# M-BOX.net
KiCad netlist of a schematic drawn in Altium Designer
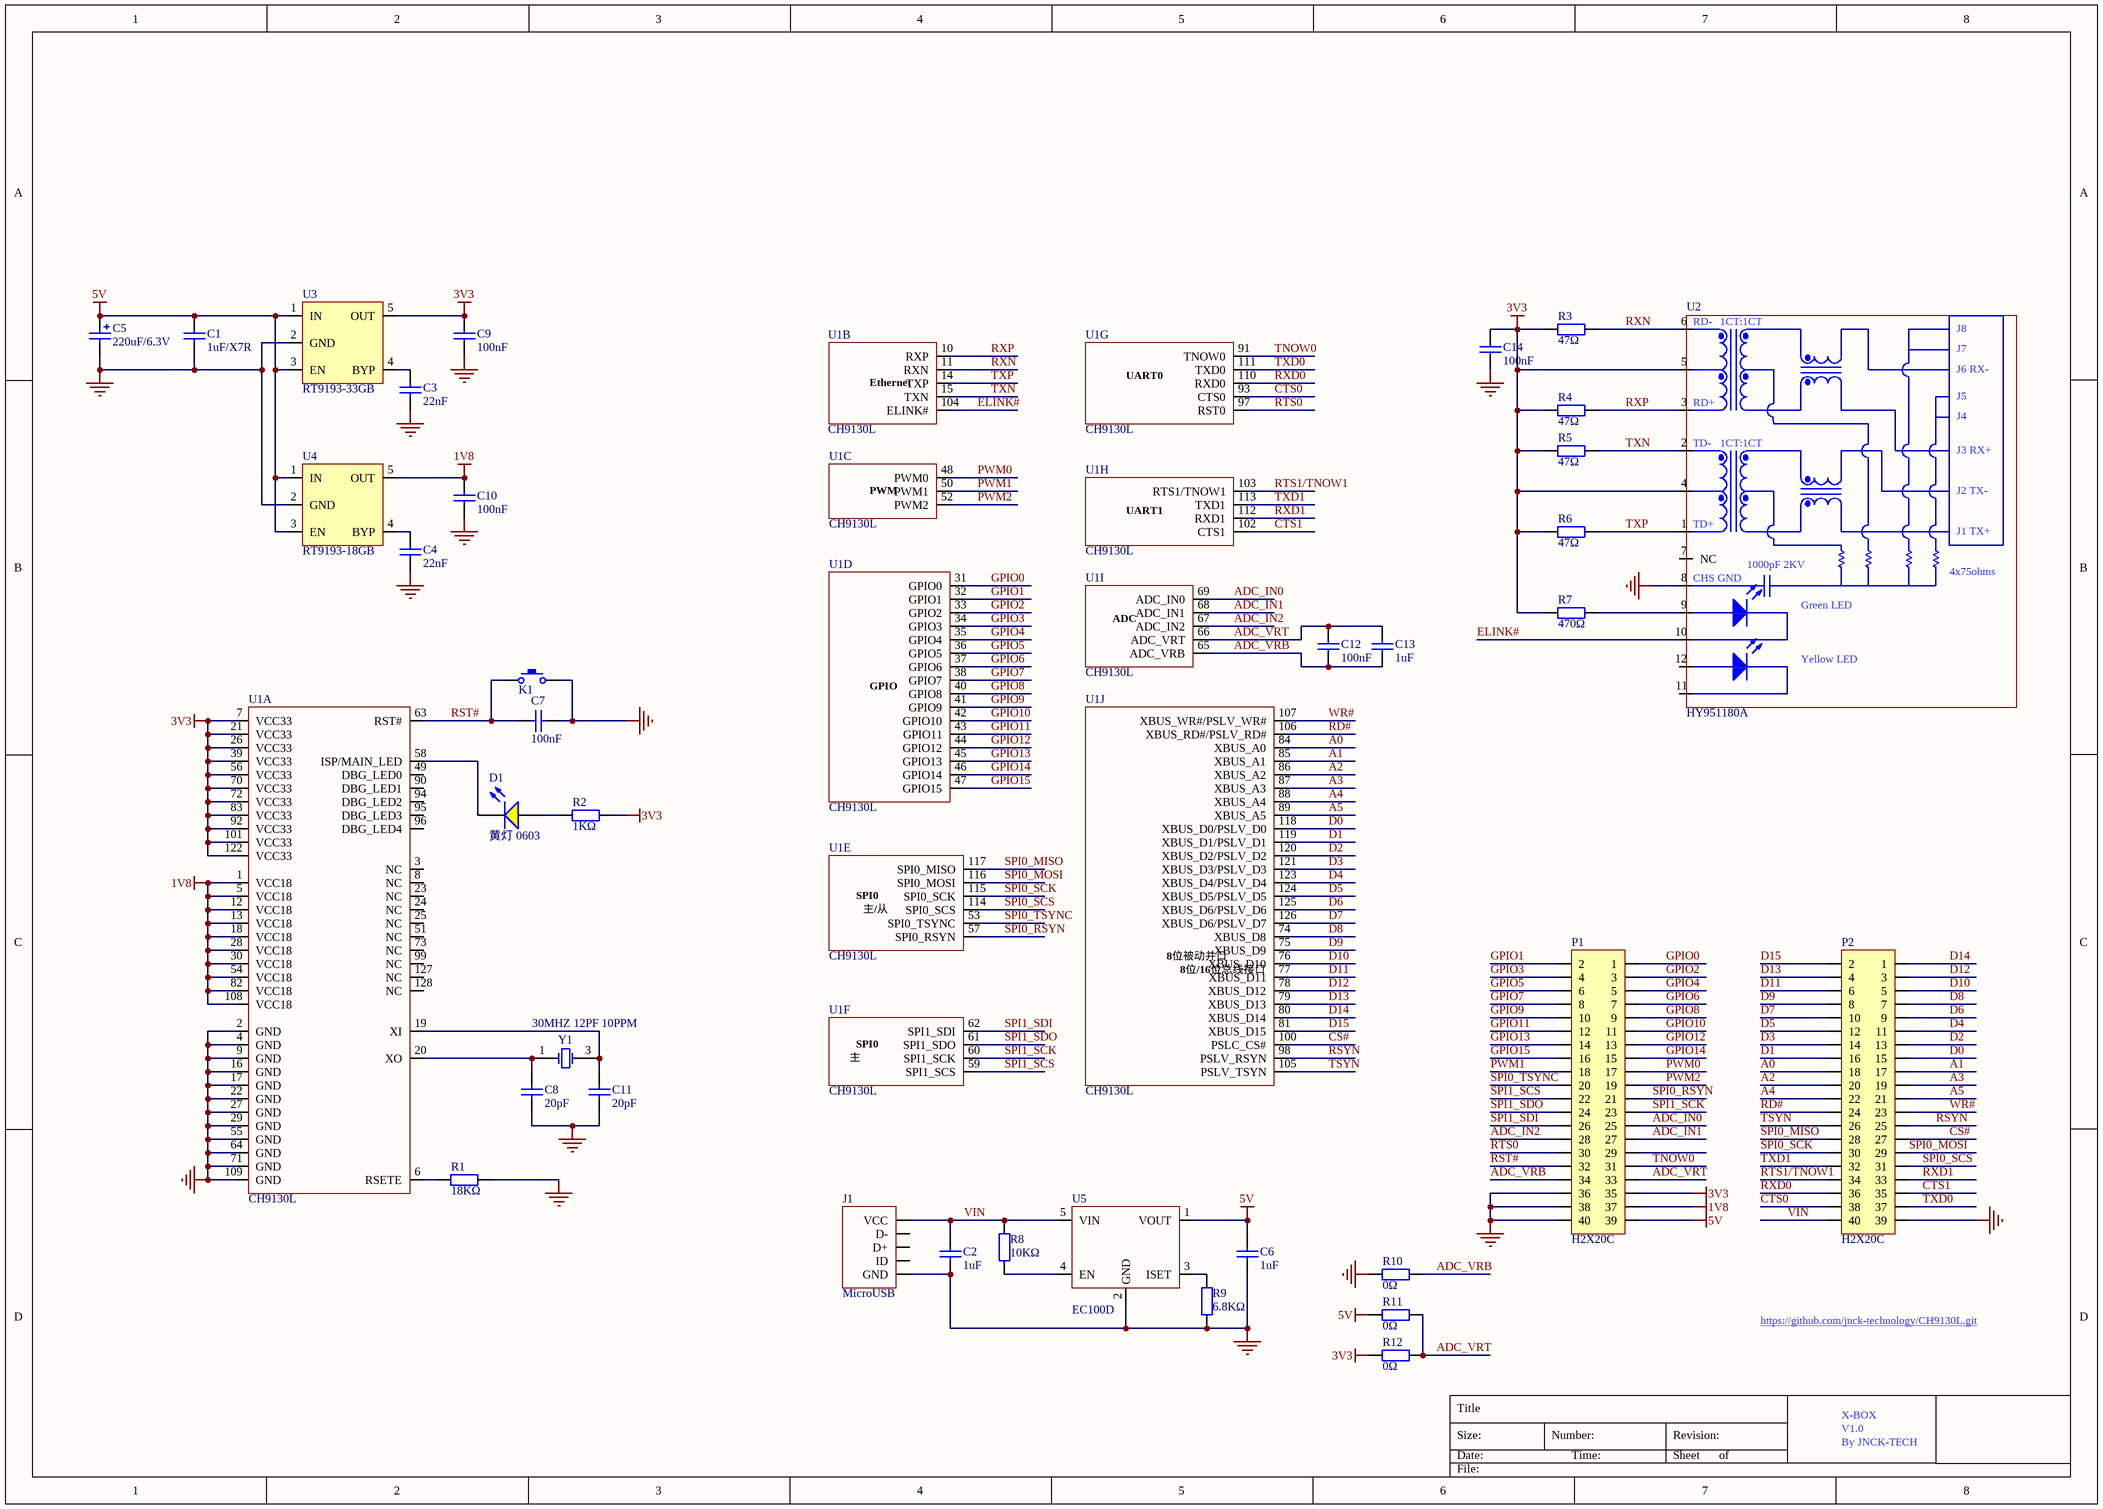
[diagram p0: M-BOX.SchDoc]

(export (version "E")
  (design (tool "Eeschema 10.0.6"))
  (components
    (comp (ref "C1")
      (value "1uF/X7R")
      (footprint "LC-0603_C")
      (description "贴片电容")
      (libsource (lib "Miscellaneous Devices LC") (part "0603 1uF (105) 10% 50V"))
    )
    (comp (ref "C2")
      (value "1uF")
      (footprint "LC-0603_C")
      (description "贴片电容")
      (libsource (lib "Miscellaneous Devices LC") (part "0603 1uF (105) 10% 50V"))
    )
    (comp (ref "C3")
      (value "22nF")
      (footprint "LC-0603_C")
      (description "贴片电容")
      (libsource (lib "Miscellaneous Devices LC") (part "0603 22nF (223) 10% 50V"))
    )
    (comp (ref "C4")
      (value "22nF")
      (footprint "LC-0603_C")
      (description "贴片电容")
      (libsource (lib "Miscellaneous Devices LC") (part "0603 22nF (223) 10% 50V"))
    )
    (comp (ref "C5")
      (value "220uF/6.3V")
      (footprint "LC-CASE-A_3216")
      (description "钽电容")
      (libsource (lib "Miscellaneous Devices LC") (part "3216 10uF (106) 10% 16V"))
    )
    (comp (ref "C6")
      (value "1uF")
      (footprint "LC-0603_C")
      (description "贴片电容")
      (libsource (lib "Miscellaneous Devices LC") (part "0603 1uF (105) 10% 50V"))
    )
    (comp (ref "C7")
      (value "100nF")
      (footprint "LC-0603_C")
      (description "贴片电容")
      (libsource (lib "Miscellaneous Devices LC") (part "0603 100nF (104) 10% 50V"))
    )
    (comp (ref "C8")
      (value "20pF")
      (footprint "LC-0603_C")
      (description "贴片电容")
      (libsource (lib "Miscellaneous Devices LC") (part "0603 20pF (200) 5% 50V"))
    )
    (comp (ref "C9")
      (value "100nF")
      (footprint "LC-0603_C")
      (description "贴片电容")
      (libsource (lib "Miscellaneous Devices LC") (part "0603 100nF (104) 10% 50V"))
    )
    (comp (ref "C10")
      (value "100nF")
      (footprint "LC-0603_C")
      (description "贴片电容")
      (libsource (lib "Miscellaneous Devices LC") (part "0603 100nF (104) 10% 50V"))
    )
    (comp (ref "C11")
      (value "20pF")
      (footprint "LC-0603_C")
      (description "贴片电容")
      (libsource (lib "Miscellaneous Devices LC") (part "0603 20pF (200) 5% 50V"))
    )
    (comp (ref "C12")
      (value "100nF")
      (footprint "LC-0603_C")
      (description "贴片电容")
      (libsource (lib "Miscellaneous Devices LC") (part "0603 100nF (104) 10% 50V"))
    )
    (comp (ref "C13")
      (value "1uF")
      (footprint "LC-0603_C")
      (description "贴片电容")
      (libsource (lib "Miscellaneous Devices LC") (part "0603 1uF (105) 10% 50V"))
    )
    (comp (ref "C14")
      (value "100nF")
      (footprint "LC-0603_C")
      (description "贴片电容")
      (libsource (lib "Miscellaneous Devices LC") (part "0603 100nF (104) 10% 50V"))
    )
    (comp (ref "D1")
      (value "黄灯 0603")
      (footprint "LC-0603_LED_S1")
      (description "发光二极管")
      (libsource (lib "Miscellaneous Devices LC") (part "0603 黄灯"))
    )
    (comp (ref "J1")
      (value "MicroUSB")
      (footprint "MicroUSB")
      (libsource (lib "MY-Standard-Library-AD") (part "MicroUSB"))
    )
    (comp (ref "K1")
      (value "TS-1107U")
      (footprint "TS-1107U")
      (description "轻触按钮")
      (fields (field (name "MANUFACTURER") "皓宇電子"))
      (libsource (lib "MY-Standard-Library-AD") (part "SW_TS-1107U"))
    )
    (comp (ref "P1")
      (value "H2X20C")
      (footprint "H2X20C")
      (description "排母/2.54mm 2*20P 长脚排座")
      (libsource (lib "MY-Standard-Library-AD") (part "H2X20C"))
    )
    (comp (ref "P2")
      (value "H2X20C")
      (footprint "H2X20C")
      (description "排母/2.54mm 2*20P 长脚排座")
      (libsource (lib "MY-Standard-Library-AD") (part "H2X20C"))
    )
    (comp (ref "R1")
      (value "18KΩ")
      (footprint "LC-0603_R")
      (description "贴片电阻")
      (libsource (lib "Miscellaneous Devices LC") (part "0603 18KΩ (1802) 1%"))
    )
    (comp (ref "R2")
      (value "1KΩ")
      (footprint "LC-0603_R")
      (description "贴片电阻")
      (libsource (lib "Miscellaneous Devices LC") (part "0603 1KΩ (1001) 1%"))
    )
    (comp (ref "R3")
      (value "47Ω")
      (footprint "LC-0603_R")
      (description "贴片电阻")
      (libsource (lib "Miscellaneous Devices LC") (part "0603 47Ω (47R0) 1%"))
    )
    (comp (ref "R4")
      (value "47Ω")
      (footprint "LC-0603_R")
      (description "贴片电阻")
      (libsource (lib "Miscellaneous Devices LC") (part "0603 47Ω (47R0) 1%"))
    )
    (comp (ref "R5")
      (value "47Ω")
      (footprint "LC-0603_R")
      (description "贴片电阻")
      (libsource (lib "Miscellaneous Devices LC") (part "0603 47Ω (47R0) 1%"))
    )
    (comp (ref "R6")
      (value "47Ω")
      (footprint "LC-0603_R")
      (description "贴片电阻")
      (libsource (lib "Miscellaneous Devices LC") (part "0603 47Ω (47R0) 1%"))
    )
    (comp (ref "R7")
      (value "470Ω")
      (footprint "LC-0603_R")
      (description "贴片电阻")
      (libsource (lib "Miscellaneous Devices LC") (part "0603 470Ω (4700) 1%"))
    )
    (comp (ref "R8")
      (value "10KΩ")
      (footprint "LC-0603_R")
      (description "贴片电阻")
      (libsource (lib "Miscellaneous Devices LC") (part "0603 10KΩ (1002) 1%"))
    )
    (comp (ref "R9")
      (value "6.8KΩ")
      (footprint "LC-0603_R")
      (description "贴片电阻")
      (libsource (lib "Miscellaneous Devices LC") (part "0603 6.8KΩ (6801) 1%"))
    )
    (comp (ref "R10")
      (value "0Ω")
      (footprint "LC-0603_R")
      (description "贴片电阻")
      (libsource (lib "Miscellaneous Devices LC") (part "0603 0Ω (0R0) 1%"))
    )
    (comp (ref "R11")
      (value "0Ω")
      (footprint "LC-0603_R")
      (description "贴片电阻")
      (libsource (lib "Miscellaneous Devices LC") (part "0603 0Ω (0R0) 1%"))
    )
    (comp (ref "R12")
      (value "0Ω")
      (footprint "LC-0603_R")
      (description "贴片电阻")
      (libsource (lib "Miscellaneous Devices LC") (part "0603 0Ω (0R0) 1%"))
    )
    (comp (ref "U1")
      (value "CH9130L")
      (footprint "LC-LQFP-128_14x14x04P")
      (description "以太网扩展多外设接口芯片")
      (fields (field (name "MANUFACTURER") "WCH(南京沁恒)"))
      (libsource (lib "MY-Standard-Library-AD") (part "CH9130L"))
    )
    (comp (ref "U2")
      (value "HY951180A")
      (footprint "HY951180A")
      (description "网口")
      (fields (field (name "MANUFACTURER") "HANRUN(汉仁)"))
      (libsource (lib "MY-Standard-Library-AD") (part "HY951180A"))
    )
    (comp (ref "U3")
      (value "RT9193-33GB")
      (footprint "LC-SOT-23-5")
      (description "RT9193 Series 300 mA 3.3 V")
      (libsource (lib "MY-Standard-Library-AD") (part "RT9193-33GB"))
    )
    (comp (ref "U4")
      (value "RT9193-18GB")
      (footprint "LC-SOT-23-5")
      (description "RT9193 Series 1.8V 300 mA")
      (libsource (lib "MY-Standard-Library-AD") (part "RT9193-18GB"))
    )
    (comp (ref "U5")
      (value "EC100D")
      (footprint "LC-SOT-23-5")
      (description "短路、过流保护芯片")
      (fields (field (name "MANUFACTURER") "FM富满"))
      (libsource (lib "MY-Standard-Library-AD") (part "EC100D"))
    )
    (comp (ref "Y1")
      (value "30MHZ 12PF 10PPM")
      (footprint "LC-SMD-3225_4P")
      (description "贴片晶振")
      (libsource (lib "Miscellaneous Devices LC") (part "SMD-3225_4P  16MHZ 9PF 10PPM"))
    )
  )
  (nets
    (net (code "1") (name "/A0") (class "Default")
      (node (ref "P2") (pin "18") (pinfunction "18_18") (pintype "passive"))
      (node (ref "U1") (pin "84") (pinfunction "XBUS_A0_84") (pintype "passive"))
    )
    (net (code "2") (name "/A1") (class "Default")
      (node (ref "P2") (pin "17") (pinfunction "17_17") (pintype "passive"))
      (node (ref "U1") (pin "85") (pinfunction "XBUS_A1_85") (pintype "passive"))
    )
    (net (code "3") (name "/A2") (class "Default")
      (node (ref "P2") (pin "20") (pinfunction "20_20") (pintype "passive"))
      (node (ref "U1") (pin "86") (pinfunction "XBUS_A2_86") (pintype "passive"))
    )
    (net (code "4") (name "/A3") (class "Default")
      (node (ref "P2") (pin "19") (pinfunction "19_19") (pintype "passive"))
      (node (ref "U1") (pin "87") (pinfunction "XBUS_A3_87") (pintype "passive"))
    )
    (net (code "5") (name "/A4") (class "Default")
      (node (ref "P2") (pin "22") (pinfunction "22_22") (pintype "passive"))
      (node (ref "U1") (pin "88") (pinfunction "XBUS_A4_88") (pintype "passive"))
    )
    (net (code "6") (name "/A5") (class "Default")
      (node (ref "P2") (pin "21") (pinfunction "21_21") (pintype "passive"))
      (node (ref "U1") (pin "89") (pinfunction "XBUS_A5_89") (pintype "passive"))
    )
    (net (code "7") (name "/ADC_IN0") (class "Default")
      (node (ref "P1") (pin "25") (pinfunction "25_25") (pintype "passive"))
      (node (ref "U1") (pin "69") (pinfunction "ADC_IN0_69") (pintype "passive"))
    )
    (net (code "8") (name "/ADC_IN1") (class "Default")
      (node (ref "P1") (pin "27") (pinfunction "27_27") (pintype "passive"))
      (node (ref "U1") (pin "68") (pinfunction "ADC_IN1_68") (pintype "passive"))
    )
    (net (code "9") (name "/ADC_IN2") (class "Default")
      (node (ref "P1") (pin "28") (pinfunction "28_28") (pintype "passive"))
      (node (ref "U1") (pin "67") (pinfunction "ADC_IN2_67") (pintype "passive"))
    )
    (net (code "10") (name "/ADC_VRB") (class "Default")
      (node (ref "C12") (pin "1") (pinfunction "1_1") (pintype "passive"))
      (node (ref "C13") (pin "1") (pinfunction "1_1") (pintype "passive"))
      (node (ref "P1") (pin "34") (pinfunction "34_34") (pintype "passive"))
      (node (ref "R10") (pin "2") (pinfunction "2_2") (pintype "passive"))
      (node (ref "U1") (pin "65") (pinfunction "ADC_VRB_65") (pintype "passive"))
    )
    (net (code "11") (name "/ADC_VRT") (class "Default")
      (node (ref "C12") (pin "2") (pinfunction "2_2") (pintype "passive"))
      (node (ref "C13") (pin "2") (pinfunction "2_2") (pintype "passive"))
      (node (ref "P1") (pin "33") (pinfunction "33_33") (pintype "passive"))
      (node (ref "R11") (pin "2") (pinfunction "2_2") (pintype "passive"))
      (node (ref "R12") (pin "2") (pinfunction "2_2") (pintype "passive"))
      (node (ref "U1") (pin "66") (pinfunction "ADC_VRT_66") (pintype "passive"))
    )
    (net (code "12") (name "/CS#") (class "Default")
      (node (ref "P2") (pin "27") (pinfunction "27_27") (pintype "passive"))
      (node (ref "U1") (pin "100") (pinfunction "PSLC_CS#_100") (pintype "passive"))
    )
    (net (code "13") (name "/CTS0") (class "Default")
      (node (ref "P2") (pin "38") (pinfunction "38_38") (pintype "passive"))
      (node (ref "U1") (pin "93") (pinfunction "CTS0_93") (pintype "passive"))
    )
    (net (code "14") (name "/CTS1") (class "Default")
      (node (ref "P2") (pin "35") (pinfunction "35_35") (pintype "passive"))
      (node (ref "U1") (pin "102") (pinfunction "CTS1_102") (pintype "passive"))
    )
    (net (code "15") (name "/D0") (class "Default")
      (node (ref "P2") (pin "15") (pinfunction "15_15") (pintype "passive"))
      (node (ref "U1") (pin "118") (pinfunction "XBUS_D0/PSLV_D0_118") (pintype "passive"))
    )
    (net (code "16") (name "/D1") (class "Default")
      (node (ref "P2") (pin "16") (pinfunction "16_16") (pintype "passive"))
      (node (ref "U1") (pin "119") (pinfunction "XBUS_D1/PSLV_D1_119") (pintype "passive"))
    )
    (net (code "17") (name "/D2") (class "Default")
      (node (ref "P2") (pin "13") (pinfunction "13_13") (pintype "passive"))
      (node (ref "U1") (pin "120") (pinfunction "XBUS_D2/PSLV_D2_120") (pintype "passive"))
    )
    (net (code "18") (name "/D3") (class "Default")
      (node (ref "P2") (pin "14") (pinfunction "14_14") (pintype "passive"))
      (node (ref "U1") (pin "121") (pinfunction "XBUS_D3/PSLV_D3_121") (pintype "passive"))
    )
    (net (code "19") (name "/D4") (class "Default")
      (node (ref "P2") (pin "11") (pinfunction "11_11") (pintype "passive"))
      (node (ref "U1") (pin "123") (pinfunction "XBUS_D4/PSLV_D4_123") (pintype "passive"))
    )
    (net (code "20") (name "/D5") (class "Default")
      (node (ref "P2") (pin "12") (pinfunction "12_12") (pintype "passive"))
      (node (ref "U1") (pin "124") (pinfunction "XBUS_D5/PSLV_D5_124") (pintype "passive"))
    )
    (net (code "21") (name "/D6") (class "Default")
      (node (ref "P2") (pin "9") (pinfunction "9_9") (pintype "passive"))
      (node (ref "U1") (pin "125") (pinfunction "XBUS_D6/PSLV_D6_125") (pintype "passive"))
    )
    (net (code "22") (name "/D7") (class "Default")
      (node (ref "P2") (pin "10") (pinfunction "10_10") (pintype "passive"))
      (node (ref "U1") (pin "126") (pinfunction "XBUS_D6/PSLV_D7_126") (pintype "passive"))
    )
    (net (code "23") (name "/D8") (class "Default")
      (node (ref "P2") (pin "7") (pinfunction "7_7") (pintype "passive"))
      (node (ref "U1") (pin "74") (pinfunction "XBUS_D8_74") (pintype "passive"))
    )
    (net (code "24") (name "/D9") (class "Default")
      (node (ref "P2") (pin "8") (pinfunction "8_8") (pintype "passive"))
      (node (ref "U1") (pin "75") (pinfunction "XBUS_D9_75") (pintype "passive"))
    )
    (net (code "25") (name "/D10") (class "Default")
      (node (ref "P2") (pin "5") (pinfunction "5_5") (pintype "passive"))
      (node (ref "U1") (pin "76") (pinfunction "XBUS_D10_76") (pintype "passive"))
    )
    (net (code "26") (name "/D11") (class "Default")
      (node (ref "P2") (pin "6") (pinfunction "6_6") (pintype "passive"))
      (node (ref "U1") (pin "77") (pinfunction "XBUS_D11_77") (pintype "passive"))
    )
    (net (code "27") (name "/D12") (class "Default")
      (node (ref "P2") (pin "3") (pinfunction "3_3") (pintype "passive"))
      (node (ref "U1") (pin "78") (pinfunction "XBUS_D12_78") (pintype "passive"))
    )
    (net (code "28") (name "/D13") (class "Default")
      (node (ref "P2") (pin "4") (pinfunction "4_4") (pintype "passive"))
      (node (ref "U1") (pin "79") (pinfunction "XBUS_D13_79") (pintype "passive"))
    )
    (net (code "29") (name "/D14") (class "Default")
      (node (ref "P2") (pin "1") (pinfunction "1_1") (pintype "passive"))
      (node (ref "U1") (pin "80") (pinfunction "XBUS_D14_80") (pintype "passive"))
    )
    (net (code "30") (name "/D15") (class "Default")
      (node (ref "P2") (pin "2") (pinfunction "2_2") (pintype "passive"))
      (node (ref "U1") (pin "81") (pinfunction "XBUS_D15_81") (pintype "passive"))
    )
    (net (code "31") (name "/ELINK#") (class "Default")
      (node (ref "U1") (pin "104") (pinfunction "ELINK#_104") (pintype "passive"))
      (node (ref "U2") (pin "10") (pinfunction "10_10") (pintype "passive"))
    )
    (net (code "32") (name "/GPIO0") (class "Default")
      (node (ref "P1") (pin "1") (pinfunction "1_1") (pintype "passive"))
      (node (ref "U1") (pin "31") (pinfunction "GPIO0_31") (pintype "passive"))
    )
    (net (code "33") (name "/GPIO1") (class "Default")
      (node (ref "P1") (pin "2") (pinfunction "2_2") (pintype "passive"))
      (node (ref "U1") (pin "32") (pinfunction "GPIO1_32") (pintype "passive"))
    )
    (net (code "34") (name "/GPIO2") (class "Default")
      (node (ref "P1") (pin "3") (pinfunction "3_3") (pintype "passive"))
      (node (ref "U1") (pin "33") (pinfunction "GPIO2_33") (pintype "passive"))
    )
    (net (code "35") (name "/GPIO3") (class "Default")
      (node (ref "P1") (pin "4") (pinfunction "4_4") (pintype "passive"))
      (node (ref "U1") (pin "34") (pinfunction "GPIO3_34") (pintype "passive"))
    )
    (net (code "36") (name "/GPIO4") (class "Default")
      (node (ref "P1") (pin "5") (pinfunction "5_5") (pintype "passive"))
      (node (ref "U1") (pin "35") (pinfunction "GPIO4_35") (pintype "passive"))
    )
    (net (code "37") (name "/GPIO5") (class "Default")
      (node (ref "P1") (pin "6") (pinfunction "6_6") (pintype "passive"))
      (node (ref "U1") (pin "36") (pinfunction "GPIO5_36") (pintype "passive"))
    )
    (net (code "38") (name "/GPIO6") (class "Default")
      (node (ref "P1") (pin "7") (pinfunction "7_7") (pintype "passive"))
      (node (ref "U1") (pin "37") (pinfunction "GPIO6_37") (pintype "passive"))
    )
    (net (code "39") (name "/GPIO7") (class "Default")
      (node (ref "P1") (pin "8") (pinfunction "8_8") (pintype "passive"))
      (node (ref "U1") (pin "38") (pinfunction "GPIO7_38") (pintype "passive"))
    )
    (net (code "40") (name "/GPIO8") (class "Default")
      (node (ref "P1") (pin "9") (pinfunction "9_9") (pintype "passive"))
      (node (ref "U1") (pin "40") (pinfunction "GPIO8_40") (pintype "passive"))
    )
    (net (code "41") (name "/GPIO9") (class "Default")
      (node (ref "P1") (pin "10") (pinfunction "10_10") (pintype "passive"))
      (node (ref "U1") (pin "41") (pinfunction "GPIO9_41") (pintype "passive"))
    )
    (net (code "42") (name "/GPIO10") (class "Default")
      (node (ref "P1") (pin "11") (pinfunction "11_11") (pintype "passive"))
      (node (ref "U1") (pin "42") (pinfunction "GPIO10_42") (pintype "passive"))
    )
    (net (code "43") (name "/GPIO11") (class "Default")
      (node (ref "P1") (pin "12") (pinfunction "12_12") (pintype "passive"))
      (node (ref "U1") (pin "43") (pinfunction "GPIO11_43") (pintype "passive"))
    )
    (net (code "44") (name "/GPIO12") (class "Default")
      (node (ref "P1") (pin "13") (pinfunction "13_13") (pintype "passive"))
      (node (ref "U1") (pin "44") (pinfunction "GPIO12_44") (pintype "passive"))
    )
    (net (code "45") (name "/GPIO13") (class "Default")
      (node (ref "P1") (pin "14") (pinfunction "14_14") (pintype "passive"))
      (node (ref "U1") (pin "45") (pinfunction "GPIO13_45") (pintype "passive"))
    )
    (net (code "46") (name "/GPIO14") (class "Default")
      (node (ref "P1") (pin "15") (pinfunction "15_15") (pintype "passive"))
      (node (ref "U1") (pin "46") (pinfunction "GPIO14_46") (pintype "passive"))
    )
    (net (code "47") (name "/GPIO15") (class "Default")
      (node (ref "P1") (pin "16") (pinfunction "16_16") (pintype "passive"))
      (node (ref "U1") (pin "47") (pinfunction "GPIO15_47") (pintype "passive"))
    )
    (net (code "48") (name "/PWM0") (class "Default")
      (node (ref "P1") (pin "17") (pinfunction "17_17") (pintype "passive"))
      (node (ref "U1") (pin "48") (pinfunction "PWM0_48") (pintype "passive"))
    )
    (net (code "49") (name "/PWM1") (class "Default")
      (node (ref "P1") (pin "18") (pinfunction "18_18") (pintype "passive"))
      (node (ref "U1") (pin "50") (pinfunction "PWM1_50") (pintype "passive"))
    )
    (net (code "50") (name "/PWM2") (class "Default")
      (node (ref "P1") (pin "19") (pinfunction "19_19") (pintype "passive"))
      (node (ref "U1") (pin "52") (pinfunction "PWM2_52") (pintype "passive"))
    )
    (net (code "51") (name "/RD#") (class "Default")
      (node (ref "P2") (pin "24") (pinfunction "24_24") (pintype "passive"))
      (node (ref "U1") (pin "106") (pinfunction "XBUS_RD#/PSLV_RD#_106") (pintype "passive"))
    )
    (net (code "52") (name "/RST#") (class "Default")
      (node (ref "C7") (pin "2") (pinfunction "2_2") (pintype "passive"))
      (node (ref "K1") (pin "1") (pinfunction "1_1") (pintype "passive"))
      (node (ref "P1") (pin "32") (pinfunction "32_32") (pintype "passive"))
      (node (ref "U1") (pin "63") (pinfunction "RST#_63") (pintype "passive"))
    )
    (net (code "53") (name "/RSYN") (class "Default")
      (node (ref "P2") (pin "25") (pinfunction "25_25") (pintype "passive"))
      (node (ref "U1") (pin "98") (pinfunction "PSLV_RSYN_98") (pintype "passive"))
    )
    (net (code "54") (name "/RTS0") (class "Default")
      (node (ref "P1") (pin "30") (pinfunction "30_30") (pintype "passive"))
      (node (ref "U1") (pin "97") (pinfunction "RST0_97") (pintype "passive"))
    )
    (net (code "55") (name "/RTS1{slash}TNOW1") (class "Default")
      (node (ref "P2") (pin "34") (pinfunction "34_34") (pintype "passive"))
      (node (ref "U1") (pin "103") (pinfunction "RTS1/TNOW1_103") (pintype "passive"))
    )
    (net (code "56") (name "/RXD0") (class "Default")
      (node (ref "P2") (pin "36") (pinfunction "36_36") (pintype "passive"))
      (node (ref "U1") (pin "110") (pinfunction "RXD0_110") (pintype "passive"))
    )
    (net (code "57") (name "/RXD1") (class "Default")
      (node (ref "P2") (pin "33") (pinfunction "33_33") (pintype "passive"))
      (node (ref "U1") (pin "112") (pinfunction "RXD1_112") (pintype "passive"))
    )
    (net (code "58") (name "/RXN") (class "Default")
      (node (ref "R3") (pin "2") (pinfunction "2_2") (pintype "passive"))
      (node (ref "U1") (pin "11") (pinfunction "RXN_11") (pintype "passive"))
      (node (ref "U2") (pin "6") (pinfunction "RD-_6") (pintype "passive"))
    )
    (net (code "59") (name "/RXP") (class "Default")
      (node (ref "R4") (pin "2") (pinfunction "2_2") (pintype "passive"))
      (node (ref "U1") (pin "10") (pinfunction "RXP_10") (pintype "passive"))
      (node (ref "U2") (pin "3") (pinfunction "RD+_3") (pintype "passive"))
    )
    (net (code "60") (name "/SPI0_MISO") (class "Default")
      (node (ref "P2") (pin "28") (pinfunction "28_28") (pintype "passive"))
      (node (ref "U1") (pin "117") (pinfunction "SPI0_MISO_117") (pintype "passive"))
    )
    (net (code "61") (name "/SPI0_MOSI") (class "Default")
      (node (ref "P2") (pin "29") (pinfunction "29_29") (pintype "passive"))
      (node (ref "U1") (pin "116") (pinfunction "SPI0_MOSI_116") (pintype "passive"))
    )
    (net (code "62") (name "/SPI0_RSYN") (class "Default")
      (node (ref "P1") (pin "21") (pinfunction "21_21") (pintype "passive"))
      (node (ref "U1") (pin "57") (pinfunction "SPI0_RSYN_57") (pintype "passive"))
    )
    (net (code "63") (name "/SPI0_SCK") (class "Default")
      (node (ref "P2") (pin "30") (pinfunction "30_30") (pintype "passive"))
      (node (ref "U1") (pin "115") (pinfunction "SPI0_SCK_115") (pintype "passive"))
    )
    (net (code "64") (name "/SPI0_SCS") (class "Default")
      (node (ref "P2") (pin "31") (pinfunction "31_31") (pintype "passive"))
      (node (ref "U1") (pin "114") (pinfunction "SPI0_SCS_114") (pintype "passive"))
    )
    (net (code "65") (name "/SPI0_TSYNC") (class "Default")
      (node (ref "P1") (pin "20") (pinfunction "20_20") (pintype "passive"))
      (node (ref "U1") (pin "53") (pinfunction "SPI0_TSYNC_53") (pintype "passive"))
    )
    (net (code "66") (name "/SPI1_SCK") (class "Default")
      (node (ref "P1") (pin "23") (pinfunction "23_23") (pintype "passive"))
      (node (ref "U1") (pin "60") (pinfunction "SPI1_SCK_60") (pintype "passive"))
    )
    (net (code "67") (name "/SPI1_SCS") (class "Default")
      (node (ref "P1") (pin "22") (pinfunction "22_22") (pintype "passive"))
      (node (ref "U1") (pin "59") (pinfunction "SPI1_SCS_59") (pintype "passive"))
    )
    (net (code "68") (name "/SPI1_SDI") (class "Default")
      (node (ref "P1") (pin "26") (pinfunction "26_26") (pintype "passive"))
      (node (ref "U1") (pin "62") (pinfunction "SPI1_SDI_62") (pintype "passive"))
    )
    (net (code "69") (name "/SPI1_SDO") (class "Default")
      (node (ref "P1") (pin "24") (pinfunction "24_24") (pintype "passive"))
      (node (ref "U1") (pin "61") (pinfunction "SPI1_SDO_61") (pintype "passive"))
    )
    (net (code "70") (name "/TNOW0") (class "Default")
      (node (ref "P1") (pin "31") (pinfunction "31_31") (pintype "passive"))
      (node (ref "U1") (pin "91") (pinfunction "TNOW0_91") (pintype "passive"))
    )
    (net (code "71") (name "/TSYN") (class "Default")
      (node (ref "P2") (pin "26") (pinfunction "26_26") (pintype "passive"))
      (node (ref "U1") (pin "105") (pinfunction "PSLV_TSYN_105") (pintype "passive"))
    )
    (net (code "72") (name "/TXD0") (class "Default")
      (node (ref "P2") (pin "37") (pinfunction "37_37") (pintype "passive"))
      (node (ref "U1") (pin "111") (pinfunction "TXD0_111") (pintype "passive"))
    )
    (net (code "73") (name "/TXD1") (class "Default")
      (node (ref "P2") (pin "32") (pinfunction "32_32") (pintype "passive"))
      (node (ref "U1") (pin "113") (pinfunction "TXD1_113") (pintype "passive"))
    )
    (net (code "74") (name "/TXN") (class "Default")
      (node (ref "R5") (pin "2") (pinfunction "2_2") (pintype "passive"))
      (node (ref "U1") (pin "15") (pinfunction "TXN_15") (pintype "passive"))
      (node (ref "U2") (pin "2") (pinfunction "TD-_2") (pintype "passive"))
    )
    (net (code "75") (name "/TXP") (class "Default")
      (node (ref "R6") (pin "2") (pinfunction "2_2") (pintype "passive"))
      (node (ref "U1") (pin "14") (pinfunction "TXP_14") (pintype "passive"))
      (node (ref "U2") (pin "1") (pinfunction "TD+_1") (pintype "passive"))
    )
    (net (code "76") (name "/VIN") (class "Default")
      (node (ref "C2") (pin "2") (pinfunction "2_2") (pintype "passive"))
      (node (ref "J1") (pin "1") (pinfunction "VCC_1") (pintype "passive"))
      (node (ref "P2") (pin "40") (pinfunction "40_40") (pintype "passive"))
      (node (ref "R8") (pin "2") (pinfunction "2_2") (pintype "passive"))
      (node (ref "U5") (pin "5") (pinfunction "VIN_5") (pintype "passive"))
    )
    (net (code "77") (name "/WR#") (class "Default")
      (node (ref "P2") (pin "23") (pinfunction "23_23") (pintype "passive"))
      (node (ref "U1") (pin "107") (pinfunction "XBUS_WR#/PSLV_WR#_107") (pintype "passive"))
    )
    (net (code "78") (name "1V8") (class "Default")
      (node (ref "C10") (pin "2") (pinfunction "2_2") (pintype "passive"))
      (node (ref "P1") (pin "37") (pinfunction "37_37") (pintype "passive"))
      (node (ref "U1") (pin "1") (pinfunction "VCC18_1") (pintype "passive"))
      (node (ref "U1") (pin "108") (pinfunction "VCC18_108") (pintype "passive"))
      (node (ref "U1") (pin "12") (pinfunction "VCC18_12") (pintype "passive"))
      (node (ref "U1") (pin "13") (pinfunction "VCC18_13") (pintype "passive"))
      (node (ref "U1") (pin "18") (pinfunction "VCC18_18") (pintype "passive"))
      (node (ref "U1") (pin "28") (pinfunction "VCC18_28") (pintype "passive"))
      (node (ref "U1") (pin "30") (pinfunction "VCC18_30") (pintype "passive"))
      (node (ref "U1") (pin "5") (pinfunction "VCC18_5") (pintype "passive"))
      (node (ref "U1") (pin "54") (pinfunction "VCC18_54") (pintype "passive"))
      (node (ref "U1") (pin "82") (pinfunction "VCC18_82") (pintype "passive"))
      (node (ref "U4") (pin "5") (pinfunction "OUT_5") (pintype "passive"))
    )
    (net (code "79") (name "3V3") (class "Default")
      (node (ref "C14") (pin "2") (pinfunction "2_2") (pintype "passive"))
      (node (ref "C9") (pin "2") (pinfunction "2_2") (pintype "passive"))
      (node (ref "P1") (pin "35") (pinfunction "35_35") (pintype "passive"))
      (node (ref "R12") (pin "1") (pinfunction "1_1") (pintype "passive"))
      (node (ref "R2") (pin "2") (pinfunction "2_2") (pintype "passive"))
      (node (ref "R3") (pin "1") (pinfunction "1_1") (pintype "passive"))
      (node (ref "R4") (pin "1") (pinfunction "1_1") (pintype "passive"))
      (node (ref "R5") (pin "1") (pinfunction "1_1") (pintype "passive"))
      (node (ref "R6") (pin "1") (pinfunction "1_1") (pintype "passive"))
      (node (ref "R7") (pin "1") (pinfunction "1_1") (pintype "passive"))
      (node (ref "U1") (pin "101") (pinfunction "VCC33_101") (pintype "passive"))
      (node (ref "U1") (pin "122") (pinfunction "VCC33_122") (pintype "passive"))
      (node (ref "U1") (pin "21") (pinfunction "VCC33_21") (pintype "passive"))
      (node (ref "U1") (pin "26") (pinfunction "VCC33_26") (pintype "passive"))
      (node (ref "U1") (pin "39") (pinfunction "VCC33_39") (pintype "passive"))
      (node (ref "U1") (pin "56") (pinfunction "VCC33_56") (pintype "passive"))
      (node (ref "U1") (pin "7") (pinfunction "VCC33_7") (pintype "passive"))
      (node (ref "U1") (pin "70") (pinfunction "VCC33_70") (pintype "passive"))
      (node (ref "U1") (pin "72") (pinfunction "VCC33_72") (pintype "passive"))
      (node (ref "U1") (pin "83") (pinfunction "VCC33_83") (pintype "passive"))
      (node (ref "U1") (pin "92") (pinfunction "VCC33_92") (pintype "passive"))
      (node (ref "U2") (pin "4") (pinfunction "4_4") (pintype "passive"))
      (node (ref "U2") (pin "5") (pinfunction "5_5") (pintype "passive"))
      (node (ref "U3") (pin "5") (pinfunction "OUT_5") (pintype "passive"))
    )
    (net (code "80") (name "5V") (class "Default")
      (node (ref "C1") (pin "2") (pinfunction "2_2") (pintype "passive"))
      (node (ref "C5") (pin "1") (pinfunction "1_1") (pintype "passive"))
      (node (ref "C6") (pin "2") (pinfunction "2_2") (pintype "passive"))
      (node (ref "P1") (pin "39") (pinfunction "39_39") (pintype "passive"))
      (node (ref "R11") (pin "1") (pinfunction "1_1") (pintype "passive"))
      (node (ref "U3") (pin "1") (pinfunction "IN_1") (pintype "passive"))
      (node (ref "U3") (pin "3") (pinfunction "EN_3") (pintype "passive"))
      (node (ref "U4") (pin "1") (pinfunction "IN_1") (pintype "passive"))
      (node (ref "U4") (pin "3") (pinfunction "EN_3") (pintype "passive"))
      (node (ref "U5") (pin "1") (pinfunction "VOUT_1") (pintype "passive"))
    )
    (net (code "81") (name "GND") (class "Default")
      (node (ref "C1") (pin "1") (pinfunction "1_1") (pintype "passive"))
      (node (ref "C10") (pin "1") (pinfunction "1_1") (pintype "passive"))
      (node (ref "C11") (pin "1") (pinfunction "1_1") (pintype "passive"))
      (node (ref "C14") (pin "1") (pinfunction "1_1") (pintype "passive"))
      (node (ref "C2") (pin "1") (pinfunction "1_1") (pintype "passive"))
      (node (ref "C3") (pin "1") (pinfunction "1_1") (pintype "passive"))
      (node (ref "C4") (pin "1") (pinfunction "1_1") (pintype "passive"))
      (node (ref "C5") (pin "2") (pinfunction "2_2") (pintype "passive"))
      (node (ref "C6") (pin "1") (pinfunction "1_1") (pintype "passive"))
      (node (ref "C7") (pin "1") (pinfunction "1_1") (pintype "passive"))
      (node (ref "C8") (pin "1") (pinfunction "1_1") (pintype "passive"))
      (node (ref "C9") (pin "1") (pinfunction "1_1") (pintype "passive"))
      (node (ref "J1") (pin "5") (pinfunction "GND_5") (pintype "passive"))
      (node (ref "K1") (pin "2") (pinfunction "2_2") (pintype "passive"))
      (node (ref "P1") (pin "36") (pinfunction "36_36") (pintype "passive"))
      (node (ref "P1") (pin "38") (pinfunction "38_38") (pintype "passive"))
      (node (ref "P1") (pin "40") (pinfunction "40_40") (pintype "passive"))
      (node (ref "P2") (pin "39") (pinfunction "39_39") (pintype "passive"))
      (node (ref "R1") (pin "2") (pinfunction "2_2") (pintype "passive"))
      (node (ref "R10") (pin "1") (pinfunction "1_1") (pintype "passive"))
      (node (ref "R9") (pin "1") (pinfunction "1_1") (pintype "passive"))
      (node (ref "U1") (pin "109") (pinfunction "GND_109") (pintype "passive"))
      (node (ref "U1") (pin "16") (pinfunction "GND_16") (pintype "passive"))
      (node (ref "U1") (pin "17") (pinfunction "GND_17") (pintype "passive"))
      (node (ref "U1") (pin "2") (pinfunction "GND_2") (pintype "passive"))
      (node (ref "U1") (pin "22") (pinfunction "GND_22") (pintype "passive"))
      (node (ref "U1") (pin "27") (pinfunction "GND_27") (pintype "passive"))
      (node (ref "U1") (pin "29") (pinfunction "GND_29") (pintype "passive"))
      (node (ref "U1") (pin "4") (pinfunction "GND_4") (pintype "passive"))
      (node (ref "U1") (pin "55") (pinfunction "GND_55") (pintype "passive"))
      (node (ref "U1") (pin "64") (pinfunction "GND_64") (pintype "passive"))
      (node (ref "U1") (pin "71") (pinfunction "GND_71") (pintype "passive"))
      (node (ref "U1") (pin "9") (pinfunction "GND_9") (pintype "passive"))
      (node (ref "U2") (pin "8") (pinfunction "GND_8") (pintype "passive"))
      (node (ref "U3") (pin "2") (pinfunction "GND_2") (pintype "passive"))
      (node (ref "U4") (pin "2") (pinfunction "GND_2") (pintype "passive"))
      (node (ref "U5") (pin "2") (pinfunction "GND_2") (pintype "passive"))
    )
    (net (code "82") (name "Net-(D1-PadA)") (class "Default")
      (node (ref "D1") (pin "A") (pinfunction "A_A") (pintype "passive"))
      (node (ref "R2") (pin "1") (pinfunction "1_1") (pintype "passive"))
    )
    (net (code "83") (name "Net-(R7-Pad2)") (class "Default")
      (node (ref "R7") (pin "2") (pinfunction "2_2") (pintype "passive"))
      (node (ref "U2") (pin "9") (pinfunction "9_9") (pintype "passive"))
    )
    (net (code "84") (name "Net-(U1A-ISP{slash}MAIN_LED)") (class "Default")
      (node (ref "D1") (pin "K") (pinfunction "K_K") (pintype "passive"))
      (node (ref "U1") (pin "58") (pinfunction "ISP/MAIN_LED_58") (pintype "passive"))
    )
    (net (code "85") (name "Net-(U1A-RSETE)") (class "Default")
      (node (ref "R1") (pin "1") (pinfunction "1_1") (pintype "passive"))
      (node (ref "U1") (pin "6") (pinfunction "RSETE_6") (pintype "passive"))
    )
    (net (code "86") (name "Net-(U1A-XI)") (class "Default")
      (node (ref "C11") (pin "2") (pinfunction "2_2") (pintype "passive"))
      (node (ref "U1") (pin "19") (pinfunction "XI_19") (pintype "passive"))
      (node (ref "Y1") (pin "3") (pinfunction "OSC2_3") (pintype "passive"))
    )
    (net (code "87") (name "Net-(U1A-XO)") (class "Default")
      (node (ref "C8") (pin "2") (pinfunction "2_2") (pintype "passive"))
      (node (ref "U1") (pin "20") (pinfunction "XO_20") (pintype "passive"))
      (node (ref "Y1") (pin "1") (pinfunction "OSC1_1") (pintype "passive"))
    )
    (net (code "88") (name "Net-(U3-BYP)") (class "Default")
      (node (ref "C3") (pin "2") (pinfunction "2_2") (pintype "passive"))
      (node (ref "U3") (pin "4") (pinfunction "BYP_4") (pintype "passive"))
    )
    (net (code "89") (name "Net-(U4-BYP)") (class "Default")
      (node (ref "C4") (pin "2") (pinfunction "2_2") (pintype "passive"))
      (node (ref "U4") (pin "4") (pinfunction "BYP_4") (pintype "passive"))
    )
    (net (code "90") (name "Net-(U5-EN)") (class "Default")
      (node (ref "R8") (pin "1") (pinfunction "1_1") (pintype "passive"))
      (node (ref "U5") (pin "4") (pinfunction "EN_4") (pintype "passive"))
    )
    (net (code "91") (name "Net-(U5-ISET)") (class "Default")
      (node (ref "R9") (pin "2") (pinfunction "2_2") (pintype "passive"))
      (node (ref "U5") (pin "3") (pinfunction "ISET_3") (pintype "passive"))
    )
    (net (code "92") (name "unconnected-(J1-D+-Pad3)") (class "Default")
      (node (ref "J1") (pin "3") (pinfunction "D+_3") (pintype "passive"))
    )
    (net (code "93") (name "unconnected-(J1-D--Pad2)") (class "Default")
      (node (ref "J1") (pin "2") (pinfunction "D-_2") (pintype "passive"))
    )
    (net (code "94") (name "unconnected-(J1-ID-Pad4)") (class "Default")
      (node (ref "J1") (pin "4") (pinfunction "ID_4") (pintype "passive"))
    )
    (net (code "95") (name "unconnected-(P1-Pad29)") (class "Default")
      (node (ref "P1") (pin "29") (pinfunction "29_29") (pintype "passive"))
    )
    (net (code "96") (name "unconnected-(U1A-DBG_LED0-Pad49)") (class "Default")
      (node (ref "U1") (pin "49") (pinfunction "DBG_LED0_49") (pintype "passive"))
    )
    (net (code "97") (name "unconnected-(U1A-DBG_LED1-Pad90)") (class "Default")
      (node (ref "U1") (pin "90") (pinfunction "DBG_LED1_90") (pintype "passive"))
    )
    (net (code "98") (name "unconnected-(U1A-DBG_LED2-Pad94)") (class "Default")
      (node (ref "U1") (pin "94") (pinfunction "DBG_LED2_94") (pintype "passive"))
    )
    (net (code "99") (name "unconnected-(U1A-DBG_LED3-Pad95)") (class "Default")
      (node (ref "U1") (pin "95") (pinfunction "DBG_LED3_95") (pintype "passive"))
    )
    (net (code "100") (name "unconnected-(U1A-DBG_LED4-Pad96)") (class "Default")
      (node (ref "U1") (pin "96") (pinfunction "DBG_LED4_96") (pintype "passive"))
    )
    (net (code "101") (name "unconnected-(U1A-NC-Pad3)") (class "Default")
      (node (ref "U1") (pin "3") (pinfunction "NC_3") (pintype "passive"))
    )
    (net (code "102") (name "unconnected-(U1A-NC-Pad8)") (class "Default")
      (node (ref "U1") (pin "8") (pinfunction "NC_8") (pintype "passive"))
    )
    (net (code "103") (name "unconnected-(U1A-NC-Pad23)") (class "Default")
      (node (ref "U1") (pin "23") (pinfunction "NC_23") (pintype "passive"))
    )
    (net (code "104") (name "unconnected-(U1A-NC-Pad24)") (class "Default")
      (node (ref "U1") (pin "24") (pinfunction "NC_24") (pintype "passive"))
    )
    (net (code "105") (name "unconnected-(U1A-NC-Pad25)") (class "Default")
      (node (ref "U1") (pin "25") (pinfunction "NC_25") (pintype "passive"))
    )
    (net (code "106") (name "unconnected-(U1A-NC-Pad51)") (class "Default")
      (node (ref "U1") (pin "51") (pinfunction "NC_51") (pintype "passive"))
    )
    (net (code "107") (name "unconnected-(U1A-NC-Pad73)") (class "Default")
      (node (ref "U1") (pin "73") (pinfunction "NC_73") (pintype "passive"))
    )
    (net (code "108") (name "unconnected-(U1A-NC-Pad99)") (class "Default")
      (node (ref "U1") (pin "99") (pinfunction "NC_99") (pintype "passive"))
    )
    (net (code "109") (name "unconnected-(U1A-NC-Pad127)") (class "Default")
      (node (ref "U1") (pin "127") (pinfunction "NC_127") (pintype "passive"))
    )
    (net (code "110") (name "unconnected-(U1A-NC-Pad128)") (class "Default")
      (node (ref "U1") (pin "128") (pinfunction "NC_128") (pintype "passive"))
    )
    (net (code "111") (name "unconnected-(U2-NC-Pad7)") (class "Default")
      (node (ref "U2") (pin "7") (pinfunction "NC_7") (pintype "passive"))
    )
    (net (code "112") (name "unconnected-(U2-Pad11)") (class "Default")
      (node (ref "U2") (pin "11") (pinfunction "11_11") (pintype "passive"))
    )
    (net (code "113") (name "unconnected-(U2-Pad12)") (class "Default")
      (node (ref "U2") (pin "12") (pinfunction "12_12") (pintype "passive"))
    )
  )
)
